# mini_board0.net
KiCad netlist of a schematic drawn in EAGLE
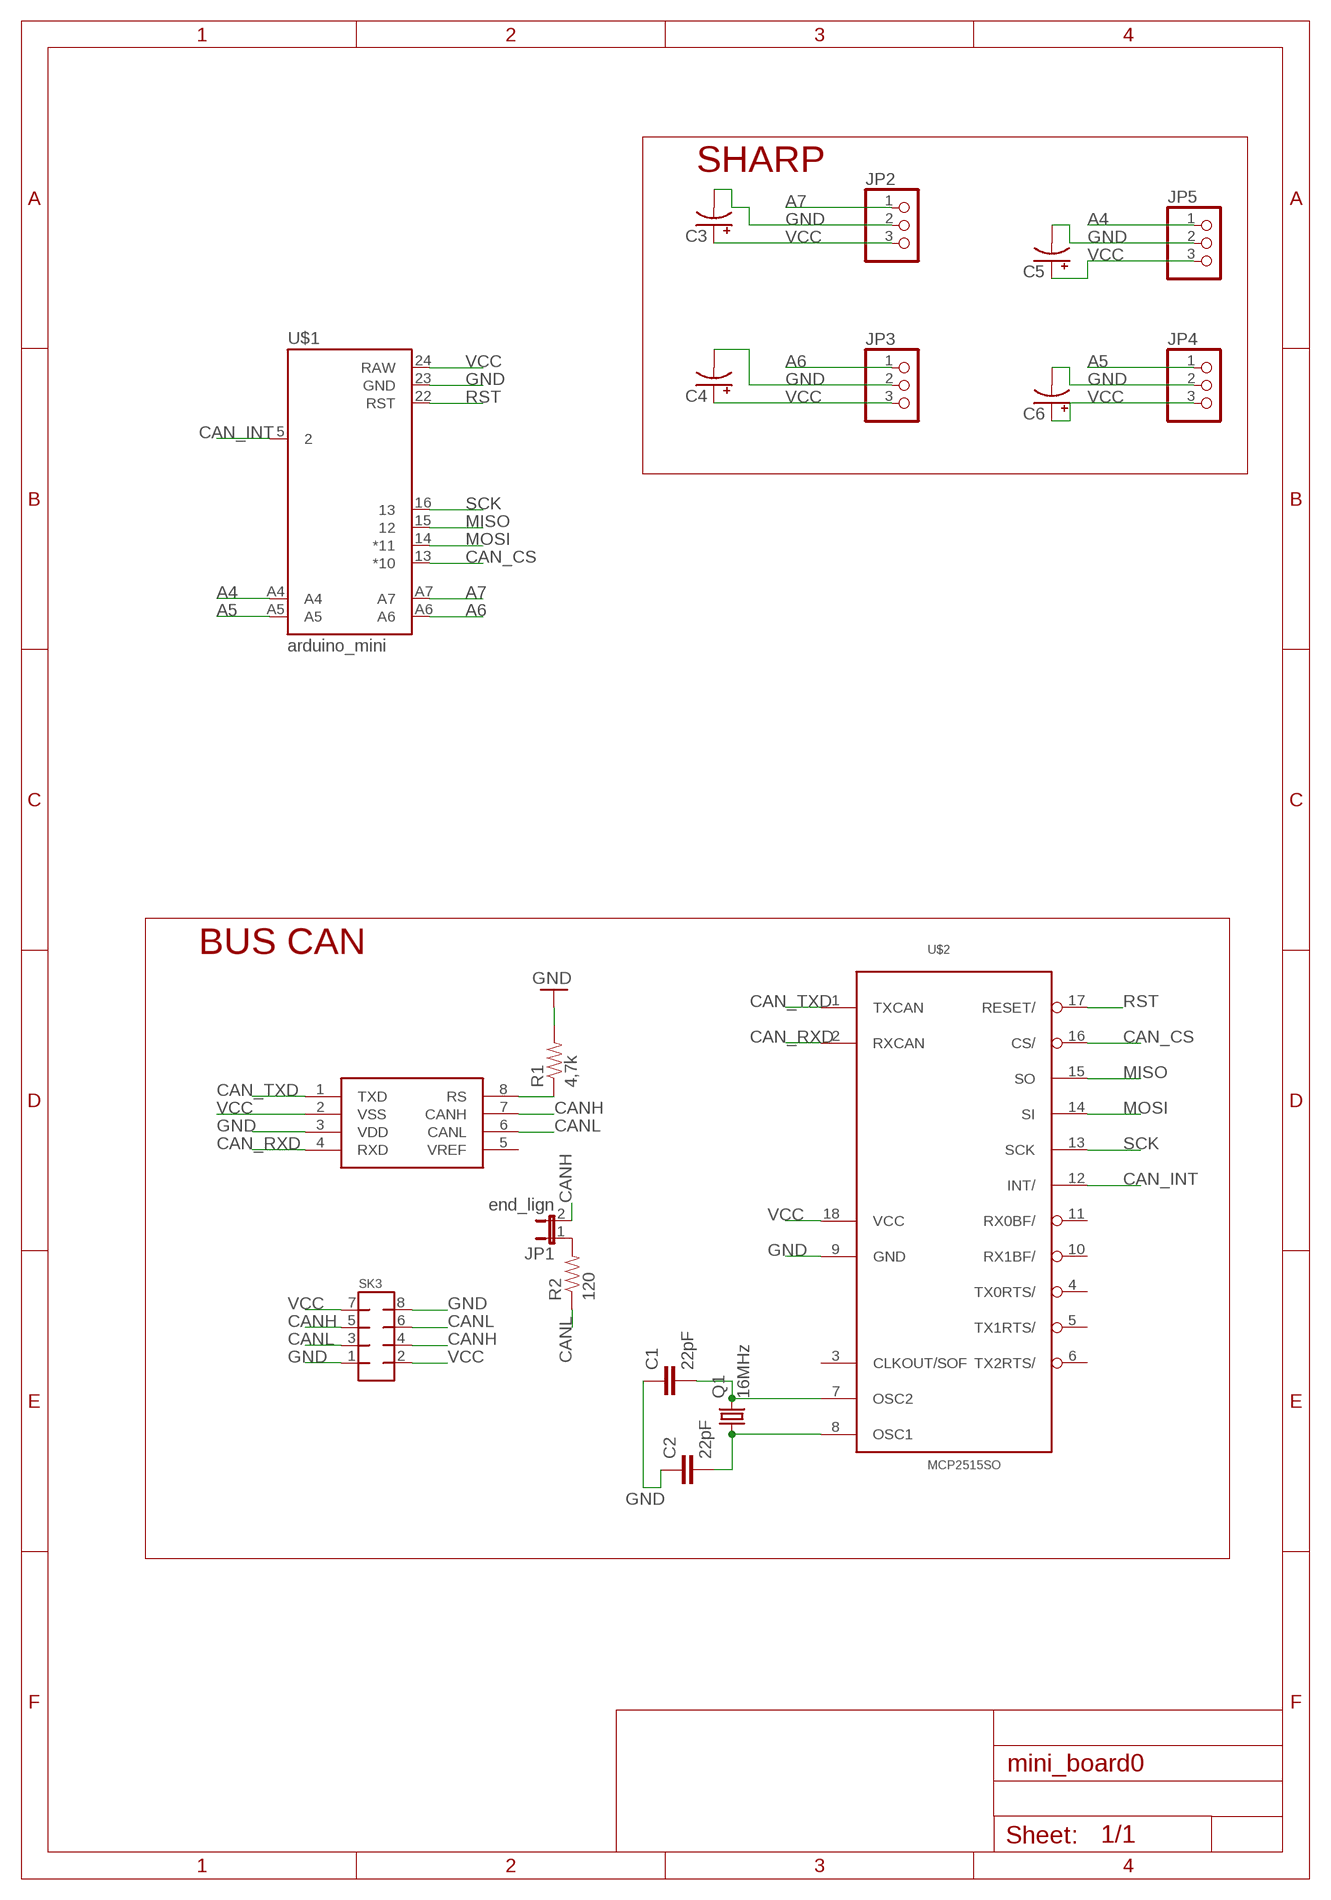
[diagram p0: schematic, sheet 1]

(export (version "E")
  (design (tool "Eeschema 10.0.6"))
  (components
    (comp (ref "C1")
      (value "22pF")
      (footprint "eagle-import:0805")
      (libsource (lib "eagle-import") (part "CAP0805"))
    )
    (comp (ref "C2")
      (value "22pF")
      (footprint "eagle-import:0805")
      (libsource (lib "eagle-import") (part "CAP0805"))
    )
    (comp (ref "C3")
      (value "CAP_POLPTH2")
      (footprint "eagle-import:CPOL-RADIAL-10UF-25V")
      (libsource (lib "eagle-import") (part "CAP_POLPTH2"))
    )
    (comp (ref "C4")
      (value "CAP_POLPTH2")
      (footprint "eagle-import:CPOL-RADIAL-10UF-25V")
      (libsource (lib "eagle-import") (part "CAP_POLPTH2"))
    )
    (comp (ref "C5")
      (value "CAP_POLPTH2")
      (footprint "eagle-import:CPOL-RADIAL-10UF-25V")
      (libsource (lib "eagle-import") (part "CAP_POLPTH2"))
    )
    (comp (ref "C6")
      (value "CAP_POLPTH2")
      (footprint "eagle-import:CPOL-RADIAL-10UF-25V")
      (libsource (lib "eagle-import") (part "CAP_POLPTH2"))
    )
    (comp (ref "JP1")
      (value "end_lign")
      (footprint "eagle-import:1X02")
      (libsource (lib "eagle-import") (part "JUMPER-2PTH"))
    )
    (comp (ref "JP2")
      (value "PINHD-1X3/90")
      (footprint "eagle-import:1X03_90")
      (libsource (lib "eagle-import") (part "PINHD-1X3/90"))
    )
    (comp (ref "JP3")
      (value "PINHD-1X3/90")
      (footprint "eagle-import:1X03_90")
      (libsource (lib "eagle-import") (part "PINHD-1X3/90"))
    )
    (comp (ref "JP4")
      (value "PINHD-1X3/90")
      (footprint "eagle-import:1X03_90")
      (libsource (lib "eagle-import") (part "PINHD-1X3/90"))
    )
    (comp (ref "JP5")
      (value "PINHD-1X3/90")
      (footprint "eagle-import:1X03_90")
      (libsource (lib "eagle-import") (part "PINHD-1X3/90"))
    )
    (comp (ref "Q1")
      (value "16MHz")
      (footprint "eagle-import:HC49_S")
      (libsource (lib "eagle-import") (part "CRYSTALHC49S"))
    )
    (comp (ref "R1")
      (value "4,7k")
      (footprint "eagle-import:0805")
      (libsource (lib "eagle-import") (part "RESISTOR0805-RES"))
    )
    (comp (ref "R2")
      (value "120")
      (footprint "eagle-import:0805")
      (libsource (lib "eagle-import") (part "RESISTOR0805-RES"))
    )
    (comp (ref "SK3")
      (value "MMATCH-8-SMT")
      (footprint "eagle-import:AMP-188275-8")
      (libsource (lib "eagle-import") (part "MMATCH-8-SMT"))
    )
    (comp (ref "U$1")
      (value "arduino_mini")
      (footprint "eagle-import:ARDUINO_PRO_MINI")
      (libsource (lib "eagle-import") (part "ARDUINO_PRO_MINISHARP_CAPE"))
    )
    (comp (ref "U$2")
      (value "MCP2515SO")
      (footprint "eagle-import:SO18L")
      (libsource (lib "eagle-import") (part "MCP2515SO"))
    )
    (comp (ref "U1")
      (value "MCP2551")
      (footprint "eagle-import:SO08")
      (libsource (lib "eagle-import") (part "MCP2551"))
    )
  )
  (nets
    (net (code "1") (name "/A4") (class "Default")
      (node (ref "JP5") (pin "1") (pinfunction "1_1") (pintype "passive"))
      (node (ref "U$1") (pin "A4") (pinfunction "A4_A4") (pintype "bidirectional"))
    )
    (net (code "2") (name "/A5") (class "Default")
      (node (ref "JP4") (pin "1") (pinfunction "1_1") (pintype "passive"))
      (node (ref "U$1") (pin "A5") (pinfunction "A5_A5") (pintype "bidirectional"))
    )
    (net (code "3") (name "/A6") (class "Default")
      (node (ref "JP3") (pin "1") (pinfunction "1_1") (pintype "passive"))
      (node (ref "U$1") (pin "A6") (pinfunction "A6_A6") (pintype "bidirectional"))
    )
    (net (code "4") (name "/A7") (class "Default")
      (node (ref "JP2") (pin "1") (pinfunction "1_1") (pintype "passive"))
      (node (ref "U$1") (pin "A7") (pinfunction "A7_A7") (pintype "bidirectional"))
    )
    (net (code "5") (name "/CANH") (class "Default")
      (node (ref "JP1") (pin "2") (pinfunction "2_2") (pintype "passive"))
      (node (ref "SK3") (pin "4") (pinfunction "4_4") (pintype "bidirectional"))
      (node (ref "SK3") (pin "5") (pinfunction "5_5") (pintype "bidirectional"))
      (node (ref "U1") (pin "7") (pinfunction "CANH_7") (pintype "bidirectional"))
    )
    (net (code "6") (name "/CANL") (class "Default")
      (node (ref "R2") (pin "1") (pinfunction "1_1") (pintype "passive"))
      (node (ref "SK3") (pin "3") (pinfunction "3_3") (pintype "bidirectional"))
      (node (ref "SK3") (pin "6") (pinfunction "6_6") (pintype "bidirectional"))
      (node (ref "U1") (pin "6") (pinfunction "CANL_6") (pintype "bidirectional"))
    )
    (net (code "7") (name "/CAN_CS") (class "Default")
      (node (ref "U$1") (pin "13") (pinfunction "*10_13") (pintype "bidirectional"))
      (node (ref "U$2") (pin "16") (pinfunction "CS/_16") (pintype "input"))
    )
    (net (code "8") (name "/CAN_INT") (class "Default")
      (node (ref "U$1") (pin "5") (pinfunction "2_5") (pintype "bidirectional"))
      (node (ref "U$2") (pin "12") (pinfunction "INT/_12") (pintype "output"))
    )
    (net (code "9") (name "/CAN_RXD") (class "Default")
      (node (ref "U$2") (pin "2") (pinfunction "RXCAN_2") (pintype "input"))
      (node (ref "U1") (pin "4") (pinfunction "RXD_4") (pintype "bidirectional"))
    )
    (net (code "10") (name "/CAN_TXD") (class "Default")
      (node (ref "U$2") (pin "1") (pinfunction "TXCAN_1") (pintype "output"))
      (node (ref "U1") (pin "1") (pinfunction "TXD_1") (pintype "bidirectional"))
    )
    (net (code "11") (name "/MISO") (class "Default")
      (node (ref "U$1") (pin "15") (pinfunction "12_15") (pintype "bidirectional"))
      (node (ref "U$2") (pin "15") (pinfunction "SO_15") (pintype "output"))
    )
    (net (code "12") (name "/MOSI") (class "Default")
      (node (ref "U$1") (pin "14") (pinfunction "*11_14") (pintype "bidirectional"))
      (node (ref "U$2") (pin "14") (pinfunction "SI_14") (pintype "input"))
    )
    (net (code "13") (name "/RST") (class "Default")
      (node (ref "U$1") (pin "22") (pinfunction "RST_22") (pintype "bidirectional"))
      (node (ref "U$2") (pin "17") (pinfunction "RESET/_17") (pintype "input"))
    )
    (net (code "14") (name "/SCK") (class "Default")
      (node (ref "U$1") (pin "16") (pinfunction "13_16") (pintype "bidirectional"))
      (node (ref "U$2") (pin "13") (pinfunction "SCK_13") (pintype "input"))
    )
    (net (code "15") (name "/VCC") (class "Default")
      (node (ref "C3") (pin "1") (pinfunction "+_1") (pintype "passive"))
      (node (ref "C4") (pin "1") (pinfunction "+_1") (pintype "passive"))
      (node (ref "C5") (pin "1") (pinfunction "+_1") (pintype "passive"))
      (node (ref "C6") (pin "1") (pinfunction "+_1") (pintype "passive"))
      (node (ref "JP2") (pin "3") (pinfunction "3_3") (pintype "passive"))
      (node (ref "JP3") (pin "3") (pinfunction "3_3") (pintype "passive"))
      (node (ref "JP4") (pin "3") (pinfunction "3_3") (pintype "passive"))
      (node (ref "JP5") (pin "3") (pinfunction "3_3") (pintype "passive"))
      (node (ref "SK3") (pin "2") (pinfunction "2_2") (pintype "bidirectional"))
      (node (ref "SK3") (pin "7") (pinfunction "7_7") (pintype "bidirectional"))
      (node (ref "U$1") (pin "24") (pinfunction "RAW_24") (pintype "bidirectional"))
      (node (ref "U$2") (pin "18") (pinfunction "VCC_18") (pintype "power_in"))
      (node (ref "U1") (pin "2") (pinfunction "VSS_2") (pintype "bidirectional"))
    )
    (net (code "16") (name "GND") (class "Default")
      (node (ref "C1") (pin "1") (pinfunction "1_1") (pintype "passive"))
      (node (ref "C2") (pin "1") (pinfunction "1_1") (pintype "passive"))
      (node (ref "C3") (pin "2") (pinfunction "-_2") (pintype "passive"))
      (node (ref "C4") (pin "2") (pinfunction "-_2") (pintype "passive"))
      (node (ref "C5") (pin "2") (pinfunction "-_2") (pintype "passive"))
      (node (ref "C6") (pin "2") (pinfunction "-_2") (pintype "passive"))
      (node (ref "JP2") (pin "2") (pinfunction "2_2") (pintype "passive"))
      (node (ref "JP3") (pin "2") (pinfunction "2_2") (pintype "passive"))
      (node (ref "JP4") (pin "2") (pinfunction "2_2") (pintype "passive"))
      (node (ref "JP5") (pin "2") (pinfunction "2_2") (pintype "passive"))
      (node (ref "R1") (pin "2") (pinfunction "2_2") (pintype "passive"))
      (node (ref "SK3") (pin "1") (pinfunction "1_1") (pintype "bidirectional"))
      (node (ref "SK3") (pin "8") (pinfunction "8_8") (pintype "bidirectional"))
      (node (ref "U$1") (pin "23") (pinfunction "GND_23") (pintype "bidirectional"))
      (node (ref "U$2") (pin "9") (pinfunction "GND_9") (pintype "power_in"))
      (node (ref "U1") (pin "3") (pinfunction "VDD_3") (pintype "bidirectional"))
    )
    (net (code "17") (name "Net-(JP1-Pad1)") (class "Default")
      (node (ref "JP1") (pin "1") (pinfunction "1_1") (pintype "passive"))
      (node (ref "R2") (pin "2") (pinfunction "2_2") (pintype "passive"))
    )
    (net (code "18") (name "Net-(U$2-OSC1)") (class "Default")
      (node (ref "C2") (pin "2") (pinfunction "2_2") (pintype "passive"))
      (node (ref "Q1") (pin "1") (pinfunction "1_1") (pintype "passive"))
      (node (ref "U$2") (pin "8") (pinfunction "OSC1_8") (pintype "bidirectional"))
    )
    (net (code "19") (name "Net-(U$2-OSC2)") (class "Default")
      (node (ref "C1") (pin "2") (pinfunction "2_2") (pintype "passive"))
      (node (ref "Q1") (pin "2") (pinfunction "2_2") (pintype "passive"))
      (node (ref "U$2") (pin "7") (pinfunction "OSC2_7") (pintype "bidirectional"))
    )
    (net (code "20") (name "Net-(U1-RS)") (class "Default")
      (node (ref "R1") (pin "1") (pinfunction "1_1") (pintype "passive"))
      (node (ref "U1") (pin "8") (pinfunction "RS_8") (pintype "bidirectional"))
    )
    (net (code "21") (name "unconnected-(U$2-CLKOUT{slash}SOF-Pad3)") (class "Default")
      (node (ref "U$2") (pin "3") (pinfunction "CLKOUT/SOF_3") (pintype "bidirectional"))
    )
    (net (code "22") (name "unconnected-(U$2-RX0BF{slash}-Pad11)") (class "Default")
      (node (ref "U$2") (pin "11") (pinfunction "RX0BF/_11") (pintype "bidirectional"))
    )
    (net (code "23") (name "unconnected-(U$2-RX1BF{slash}-Pad10)") (class "Default")
      (node (ref "U$2") (pin "10") (pinfunction "RX1BF/_10") (pintype "bidirectional"))
    )
    (net (code "24") (name "unconnected-(U$2-TX0RTS{slash}-Pad4)") (class "Default")
      (node (ref "U$2") (pin "4") (pinfunction "TX0RTS/_4") (pintype "bidirectional"))
    )
    (net (code "25") (name "unconnected-(U$2-TX1RTS{slash}-Pad5)") (class "Default")
      (node (ref "U$2") (pin "5") (pinfunction "TX1RTS/_5") (pintype "bidirectional"))
    )
    (net (code "26") (name "unconnected-(U$2-TX2RTS{slash}-Pad6)") (class "Default")
      (node (ref "U$2") (pin "6") (pinfunction "TX2RTS/_6") (pintype "bidirectional"))
    )
    (net (code "27") (name "unconnected-(U1-VREF-Pad5)") (class "Default")
      (node (ref "U1") (pin "5") (pinfunction "VREF_5") (pintype "bidirectional"))
    )
  )
)
